# USB.net
KiCad netlist of a schematic drawn in Altium Designer
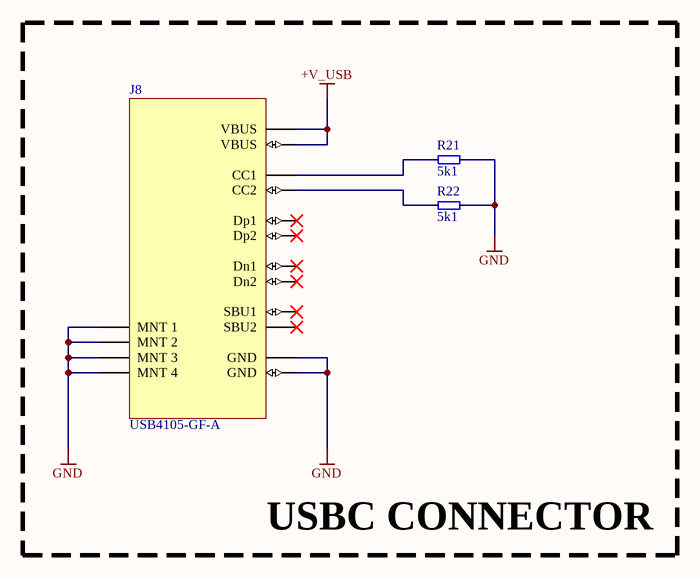
[diagram p0: USB.SchDoc]

(export (version "E")
  (design (tool "Eeschema 10.0.6"))
  (components
    (comp (ref "J8")
      (value "USB4105-GF-A")
      (footprint "FP-USB4105-GF-A-MFG")
      (description "USB Connector, 24 Contact(s), Female, Right Angle, Solder Terminal, Locking, Receptacle")
      (fields (field (name "MANUFACTURER") "GCT"))
      (libsource (lib "PolSl Racing - Electrical") (part "e7c17a616881a82b79941196b4bec10"))
    )
    (comp (ref "R21")
      (value "5k1")
      (footprint "R0402")
      (description "Generic 0402 SMD Resistor")
      (libsource (lib "PolSl Racing - Electrical") (part "Resistor"))
    )
    (comp (ref "R22")
      (value "5k1")
      (footprint "R0402")
      (description "Generic 0402 SMD Resistor")
      (libsource (lib "PolSl Racing - Electrical") (part "Resistor"))
    )
  )
  (nets
    (net (code "1") (name "+V_USB") (class "Default")
      (node (ref "J8") (pin "A4-B9") (pinfunction "VBUS_A4-B9") (pintype "power_in"))
      (node (ref "J8") (pin "B4-A9") (pinfunction "VBUS_B4-A9") (pintype "bidirectional"))
    )
    (net (code "2") (name "GND") (class "Default")
      (node (ref "J8") (pin "1") (pinfunction "MNT_1_1") (pintype "power_in"))
      (node (ref "J8") (pin "2") (pinfunction "MNT_2_2") (pintype "power_in"))
      (node (ref "J8") (pin "3") (pinfunction "MNT_3_3") (pintype "power_in"))
      (node (ref "J8") (pin "4") (pinfunction "MNT_4_4") (pintype "power_in"))
      (node (ref "J8") (pin "A1-B12") (pinfunction "GND_A1-B12") (pintype "power_in"))
      (node (ref "J8") (pin "B1-A12") (pinfunction "GND_B1-A12") (pintype "bidirectional"))
      (node (ref "R21") (pin "2") (pinfunction "2_2") (pintype "passive"))
      (node (ref "R22") (pin "2") (pinfunction "2_2") (pintype "passive"))
    )
    (net (code "3") (name "Net-(J8-CC1)") (class "Default")
      (node (ref "J8") (pin "A5") (pinfunction "CC1_A5") (pintype "power_in"))
      (node (ref "R21") (pin "1") (pinfunction "1_1") (pintype "passive"))
    )
    (net (code "4") (name "Net-(J8-CC2)") (class "Default")
      (node (ref "J8") (pin "B5") (pinfunction "CC2_B5") (pintype "bidirectional"))
      (node (ref "R22") (pin "1") (pinfunction "1_1") (pintype "passive"))
    )
    (net (code "5") (name "unconnected-(J8-Dn1-PadA7)") (class "Default")
      (node (ref "J8") (pin "A7") (pinfunction "Dn1_A7") (pintype "bidirectional+no_connect"))
    )
    (net (code "6") (name "unconnected-(J8-Dn2-PadB7)") (class "Default")
      (node (ref "J8") (pin "B7") (pinfunction "Dn2_B7") (pintype "bidirectional+no_connect"))
    )
    (net (code "7") (name "unconnected-(J8-Dp1-PadA6)") (class "Default")
      (node (ref "J8") (pin "A6") (pinfunction "Dp1_A6") (pintype "bidirectional+no_connect"))
    )
    (net (code "8") (name "unconnected-(J8-Dp2-PadB6)") (class "Default")
      (node (ref "J8") (pin "B6") (pinfunction "Dp2_B6") (pintype "bidirectional+no_connect"))
    )
    (net (code "9") (name "unconnected-(J8-SBU1-PadA8)") (class "Default")
      (node (ref "J8") (pin "A8") (pinfunction "SBU1_A8") (pintype "bidirectional+no_connect"))
    )
    (net (code "10") (name "unconnected-(J8-SBU2-PadB8)") (class "Default")
      (node (ref "J8") (pin "B8") (pinfunction "SBU2_B8") (pintype "power_in+no_connect"))
    )
  )
)
